# 555.net
KiCad netlist of a schematic drawn in EAGLE
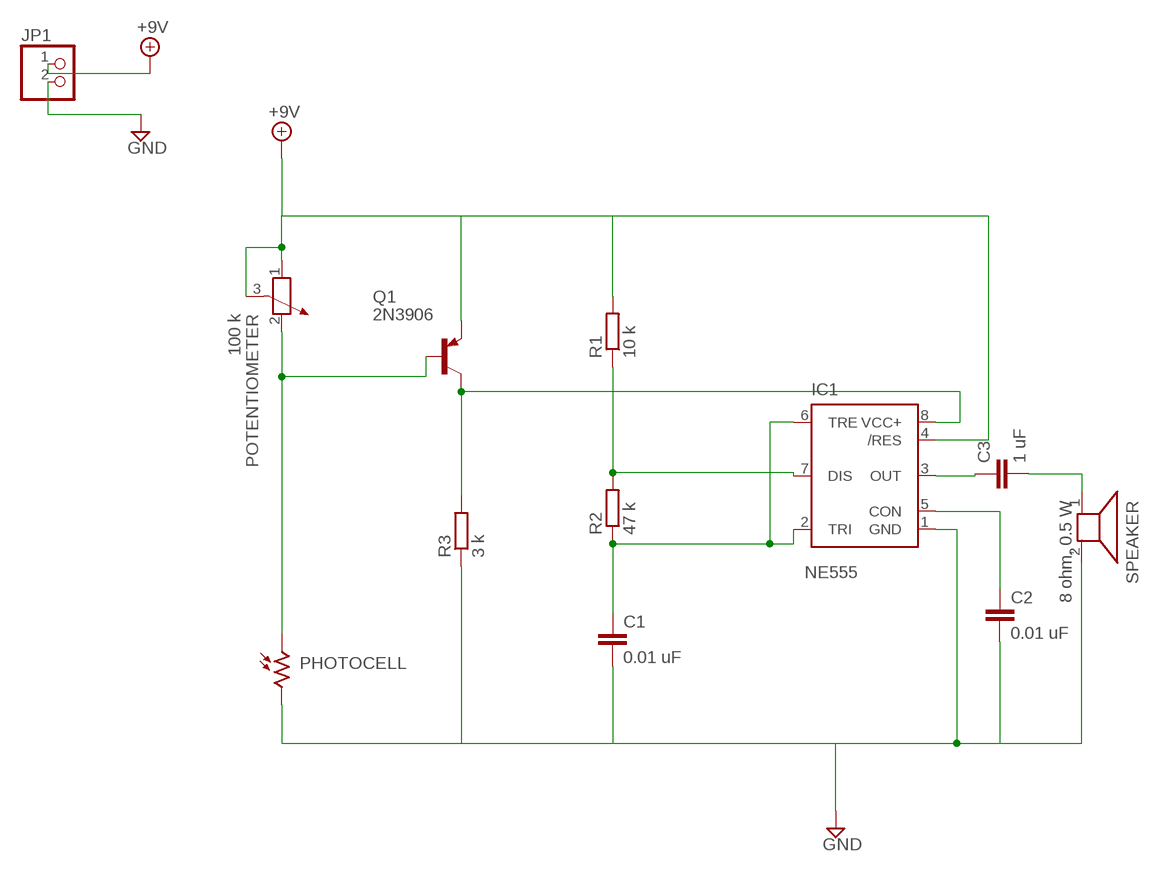
[diagram p0: schematic, sheet 1]

(export (version "E")
  (design (tool "Eeschema 10.0.6"))
  (components
    (comp (ref "C1")
      (value "0.01 uF")
      (footprint "eagle-import:C025-025X050")
      (libsource (lib "eagle-import") (part "C-EU025-025X050"))
    )
    (comp (ref "C2")
      (value "0.01 uF")
      (footprint "eagle-import:C025-025X050")
      (libsource (lib "eagle-import") (part "C-EU025-025X050"))
    )
    (comp (ref "C3")
      (value "1 uF")
      (footprint "eagle-import:C025-025X050")
      (libsource (lib "eagle-import") (part "C-EU025-025X050"))
    )
    (comp (ref "IC1")
      (value "NE555")
      (footprint "eagle-import:DIL-08")
      (fields (field (name "MF") "Arrow Electronics") (field (name "MPN") "NE555N"))
      (libsource (lib "eagle-import") (part "NE555"))
    )
    (comp (ref "JP1")
      (value "PINHD-1X2")
      (footprint "eagle-import:1X02")
      (libsource (lib "eagle-import") (part "PINHD-1X2"))
    )
    (comp (ref "PHOTOCELL")
      (value "PHOTOCELLW55")
      (footprint "eagle-import:W55XX_H")
      (libsource (lib "eagle-import") (part "PHOTOCELLW55"))
    )
    (comp (ref "POTENTIOMETER")
      (value "100 k")
      (footprint "eagle-import:PT-10")
      (libsource (lib "eagle-import") (part "POTENTIOMETER_PT-10"))
    )
    (comp (ref "Q1")
      (value "2N3906")
      (footprint "eagle-import:TO92")
      (libsource (lib "eagle-import") (part "2N3906"))
    )
    (comp (ref "R1")
      (value "10 k")
      (footprint "eagle-import:0204_7")
      (libsource (lib "eagle-import") (part "R-EU_0204/7"))
    )
    (comp (ref "R2")
      (value "47 k")
      (footprint "eagle-import:0204_7")
      (libsource (lib "eagle-import") (part "R-EU_0204/7"))
    )
    (comp (ref "R3")
      (value "3 k")
      (footprint "eagle-import:0204_7")
      (libsource (lib "eagle-import") (part "R-EU_0204/7"))
    )
    (comp (ref "SPEAKER")
      (value "8 ohm, 0.5 W")
      (footprint "eagle-import:AL60P")
      (libsource (lib "eagle-import") (part "AL60P"))
    )
  )
  (nets
    (net (code "1") (name "+9V") (class "Default")
      (node (ref "IC1") (pin "4") (pinfunction "/RES_4") (pintype "input"))
      (node (ref "JP1") (pin "1") (pinfunction "1_1") (pintype "passive"))
      (node (ref "POTENTIOMETER") (pin "1") (pinfunction "1_1") (pintype "passive"))
      (node (ref "POTENTIOMETER") (pin "3") (pinfunction "3_3") (pintype "passive"))
      (node (ref "Q1") (pin "3") (pinfunction "E_3") (pintype "passive"))
      (node (ref "R1") (pin "2") (pinfunction "2_2") (pintype "passive"))
    )
    (net (code "2") (name "GND") (class "Default")
      (node (ref "C1") (pin "2") (pinfunction "2_2") (pintype "passive"))
      (node (ref "C2") (pin "2") (pinfunction "2_2") (pintype "passive"))
      (node (ref "IC1") (pin "1") (pinfunction "GND_1") (pintype "power_in"))
      (node (ref "JP1") (pin "2") (pinfunction "2_2") (pintype "passive"))
      (node (ref "PHOTOCELL") (pin "2") (pinfunction "2_2") (pintype "passive"))
      (node (ref "R3") (pin "1") (pinfunction "1_1") (pintype "passive"))
      (node (ref "SPEAKER") (pin "2") (pinfunction "2_2") (pintype "passive"))
    )
    (net (code "3") (name "Net-(C3-Pad2)") (class "Default")
      (node (ref "C3") (pin "2") (pinfunction "2_2") (pintype "passive"))
      (node (ref "SPEAKER") (pin "1") (pinfunction "1_1") (pintype "passive"))
    )
    (net (code "4") (name "Net-(IC1-CON)") (class "Default")
      (node (ref "C2") (pin "1") (pinfunction "1_1") (pintype "passive"))
      (node (ref "IC1") (pin "5") (pinfunction "CON_5") (pintype "input"))
    )
    (net (code "5") (name "Net-(IC1-DIS)") (class "Default")
      (node (ref "IC1") (pin "7") (pinfunction "DIS_7") (pintype "input"))
      (node (ref "R1") (pin "1") (pinfunction "1_1") (pintype "passive"))
      (node (ref "R2") (pin "2") (pinfunction "2_2") (pintype "passive"))
    )
    (net (code "6") (name "Net-(IC1-OUT)") (class "Default")
      (node (ref "C3") (pin "1") (pinfunction "1_1") (pintype "passive"))
      (node (ref "IC1") (pin "3") (pinfunction "OUT_3") (pintype "output"))
    )
    (net (code "7") (name "Net-(IC1-TRI)") (class "Default")
      (node (ref "C1") (pin "1") (pinfunction "1_1") (pintype "passive"))
      (node (ref "IC1") (pin "2") (pinfunction "TRI_2") (pintype "input"))
      (node (ref "R2") (pin "1") (pinfunction "1_1") (pintype "passive"))
    )
    (net (code "8") (name "Net-(IC1-VCC+)") (class "Default")
      (node (ref "IC1") (pin "8") (pinfunction "VCC+_8") (pintype "power_in"))
      (node (ref "Q1") (pin "1") (pinfunction "C_1") (pintype "passive"))
      (node (ref "R3") (pin "2") (pinfunction "2_2") (pintype "passive"))
    )
    (net (code "9") (name "Net-(Q1-B)") (class "Default")
      (node (ref "PHOTOCELL") (pin "1") (pinfunction "1_1") (pintype "passive"))
      (node (ref "POTENTIOMETER") (pin "2") (pinfunction "2_2") (pintype "passive"))
      (node (ref "Q1") (pin "2") (pinfunction "B_2") (pintype "passive"))
    )
    (net (code "10") (name "unconnected-(IC1-TRE-Pad6)") (class "Default")
      (node (ref "IC1") (pin "6") (pinfunction "TRE_6") (pintype "input"))
    )
  )
)
